# tablespoon.net
KiCad netlist of a schematic drawn in EAGLE
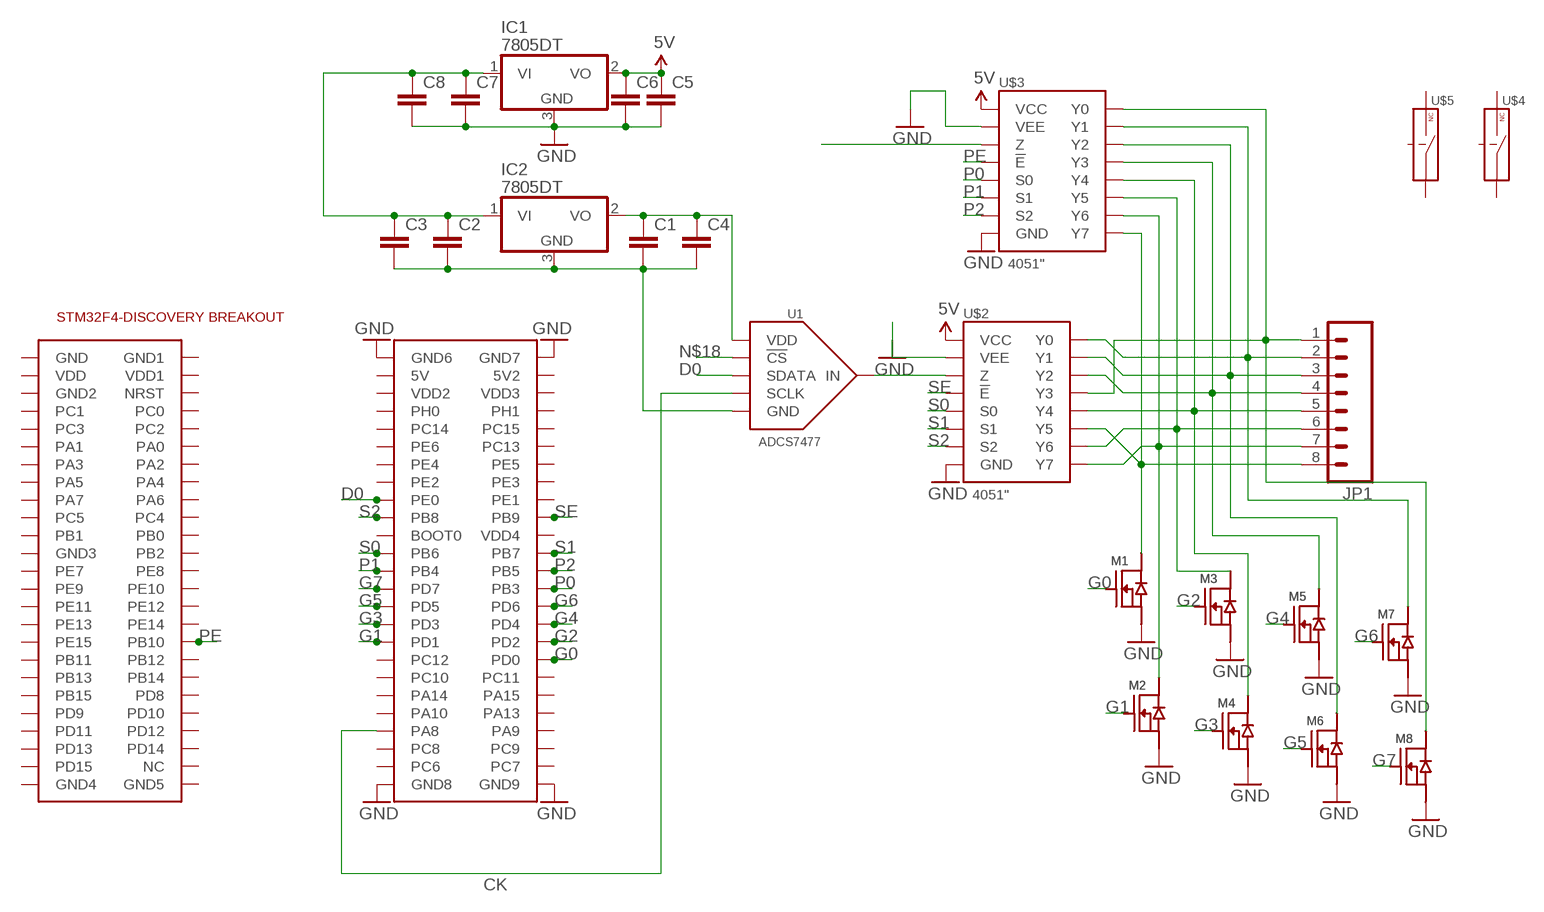
[diagram p0: schematic, sheet 1]

(export (version "E")
  (design (tool "Eeschema 10.0.6"))
  (components
    (comp (ref "C1")
      (value "C-EUC0805")
      (footprint "eagle-import:C0805")
      (libsource (lib "eagle-import") (part "C-EUC0805"))
    )
    (comp (ref "C2")
      (value "C-EUC0805")
      (footprint "eagle-import:C0805")
      (libsource (lib "eagle-import") (part "C-EUC0805"))
    )
    (comp (ref "C3")
      (value "C-EUC0805")
      (footprint "eagle-import:C0805")
      (libsource (lib "eagle-import") (part "C-EUC0805"))
    )
    (comp (ref "C4")
      (value "C-EUC0805")
      (footprint "eagle-import:C0805")
      (libsource (lib "eagle-import") (part "C-EUC0805"))
    )
    (comp (ref "C5")
      (value "C-EUC0805")
      (footprint "eagle-import:C0805")
      (libsource (lib "eagle-import") (part "C-EUC0805"))
    )
    (comp (ref "C6")
      (value "C-EUC0805")
      (footprint "eagle-import:C0805")
      (libsource (lib "eagle-import") (part "C-EUC0805"))
    )
    (comp (ref "C7")
      (value "C-EUC0805")
      (footprint "eagle-import:C0805")
      (libsource (lib "eagle-import") (part "C-EUC0805"))
    )
    (comp (ref "C8")
      (value "C-EUC0805")
      (footprint "eagle-import:C0805")
      (libsource (lib "eagle-import") (part "C-EUC0805"))
    )
    (comp (ref "IC1")
      (value "7805DT")
      (footprint "eagle-import:TO252")
      (libsource (lib "eagle-import") (part "78DT05"))
    )
    (comp (ref "IC2")
      (value "7805DT")
      (footprint "eagle-import:TO252")
      (libsource (lib "eagle-import") (part "78DT05"))
    )
    (comp (ref "JP1")
      (value "M08LONGPADS")
      (footprint "eagle-import:1X08_LONGPADS")
      (libsource (lib "eagle-import") (part "M08LONGPADS"))
    )
    (comp (ref "M1")
      (value "N-FET")
      (footprint "eagle-import:SOT23-3")
      (libsource (lib "eagle-import") (part "N-FET"))
    )
    (comp (ref "M2")
      (value "N-FET")
      (footprint "eagle-import:SOT23-3")
      (libsource (lib "eagle-import") (part "N-FET"))
    )
    (comp (ref "M3")
      (value "N-FET")
      (footprint "eagle-import:SOT23-3")
      (libsource (lib "eagle-import") (part "N-FET"))
    )
    (comp (ref "M4")
      (value "N-FET")
      (footprint "eagle-import:SOT23-3")
      (libsource (lib "eagle-import") (part "N-FET"))
    )
    (comp (ref "M5")
      (value "N-FET")
      (footprint "eagle-import:SOT23-3")
      (libsource (lib "eagle-import") (part "N-FET"))
    )
    (comp (ref "M6")
      (value "N-FET")
      (footprint "eagle-import:SOT23-3")
      (libsource (lib "eagle-import") (part "N-FET"))
    )
    (comp (ref "M7")
      (value "N-FET")
      (footprint "eagle-import:SOT23-3")
      (libsource (lib "eagle-import") (part "N-FET"))
    )
    (comp (ref "M8")
      (value "N-FET")
      (footprint "eagle-import:SOT23-3")
      (libsource (lib "eagle-import") (part "N-FET"))
    )
    (comp (ref "U$1")
      (value "STM32F4-DISCOVERY")
      (footprint "eagle-import:STM32F4-DISCOVERY")
      (libsource (lib "eagle-import") (part "STM32F4-DISCOVERY"))
    )
    (comp (ref "U$2")
      (value "4051\"")
      (footprint "eagle-import:TSSOP-16")
      (libsource (lib "eagle-import") (part "4051{dblquote}"))
    )
    (comp (ref "U$3")
      (value "4051\"")
      (footprint "eagle-import:TSSOP-16")
      (libsource (lib "eagle-import") (part "4051{dblquote}"))
    )
    (comp (ref "U$4")
      (value "DG467")
      (footprint "eagle-import:TSSOP-6")
      (libsource (lib "eagle-import") (part "DG467"))
    )
    (comp (ref "U$5")
      (value "DG467")
      (footprint "eagle-import:TSSOP-6")
      (libsource (lib "eagle-import") (part "DG467"))
    )
    (comp (ref "U1")
      (value "ADCS7477")
      (footprint "eagle-import:SOT-23-6")
      (libsource (lib "eagle-import") (part "ADCS7477"))
    )
  )
  (nets
    (net (code "1") (name "/CK") (class "Default")
      (node (ref "U$1") (pin "P$93") (pinfunction "PA8_P$93") (pintype "bidirectional"))
      (node (ref "U1") (pin "P$4") (pinfunction "SCLK_P$4") (pintype "bidirectional"))
    )
    (net (code "2") (name "/D0") (class "Default")
      (node (ref "U$1") (pin "P$67") (pinfunction "PE0_P$67") (pintype "bidirectional"))
      (node (ref "U1") (pin "P$5") (pinfunction "SDATA_P$5") (pintype "bidirectional"))
    )
    (net (code "3") (name "/G0") (class "Default")
      (node (ref "M1") (pin "1") (pinfunction "G_1") (pintype "bidirectional"))
      (node (ref "U$1") (pin "P$86") (pinfunction "PD0_P$86") (pintype "bidirectional"))
    )
    (net (code "4") (name "/G1") (class "Default")
      (node (ref "M2") (pin "1") (pinfunction "G_1") (pintype "bidirectional"))
      (node (ref "U$1") (pin "P$83") (pinfunction "PD1_P$83") (pintype "bidirectional"))
    )
    (net (code "5") (name "/G2") (class "Default")
      (node (ref "M3") (pin "1") (pinfunction "G_1") (pintype "bidirectional"))
      (node (ref "U$1") (pin "P$84") (pinfunction "PD2_P$84") (pintype "bidirectional"))
    )
    (net (code "6") (name "/G3") (class "Default")
      (node (ref "M4") (pin "1") (pinfunction "G_1") (pintype "bidirectional"))
      (node (ref "U$1") (pin "P$81") (pinfunction "PD3_P$81") (pintype "bidirectional"))
    )
    (net (code "7") (name "/G4") (class "Default")
      (node (ref "M5") (pin "1") (pinfunction "G_1") (pintype "bidirectional"))
      (node (ref "U$1") (pin "P$82") (pinfunction "PD4_P$82") (pintype "bidirectional"))
    )
    (net (code "8") (name "/G5") (class "Default")
      (node (ref "M6") (pin "1") (pinfunction "G_1") (pintype "bidirectional"))
      (node (ref "U$1") (pin "P$79") (pinfunction "PD5_P$79") (pintype "bidirectional"))
    )
    (net (code "9") (name "/G6") (class "Default")
      (node (ref "M7") (pin "1") (pinfunction "G_1") (pintype "bidirectional"))
      (node (ref "U$1") (pin "P$80") (pinfunction "PD6_P$80") (pintype "bidirectional"))
    )
    (net (code "10") (name "/G7") (class "Default")
      (node (ref "M8") (pin "1") (pinfunction "G_1") (pintype "bidirectional"))
      (node (ref "U$1") (pin "P$77") (pinfunction "PD7_P$77") (pintype "bidirectional"))
    )
    (net (code "11") (name "/N$18") (class "Default")
      (node (ref "U1") (pin "P$6") (pinfunction "~{CS}_P$6") (pintype "bidirectional"))
    )
    (net (code "12") (name "/P0") (class "Default")
      (node (ref "U$1") (pin "P$78") (pinfunction "PB3_P$78") (pintype "bidirectional"))
      (node (ref "U$3") (pin "P$11") (pinfunction "S0_P$11") (pintype "bidirectional"))
    )
    (net (code "13") (name "/P1") (class "Default")
      (node (ref "U$1") (pin "P$75") (pinfunction "PB4_P$75") (pintype "bidirectional"))
      (node (ref "U$3") (pin "P$10") (pinfunction "S1_P$10") (pintype "bidirectional"))
    )
    (net (code "14") (name "/P2") (class "Default")
      (node (ref "U$1") (pin "P$76") (pinfunction "PB5_P$76") (pintype "bidirectional"))
      (node (ref "U$3") (pin "P$9") (pinfunction "S2_P$9") (pintype "bidirectional"))
    )
    (net (code "15") (name "/PE") (class "Default")
      (node (ref "U$1") (pin "P$34") (pinfunction "PB10_P$34") (pintype "bidirectional"))
      (node (ref "U$3") (pin "P$6") (pinfunction "~{E}_P$6") (pintype "bidirectional"))
    )
    (net (code "16") (name "/S0") (class "Default")
      (node (ref "U$1") (pin "P$73") (pinfunction "PB6_P$73") (pintype "bidirectional"))
      (node (ref "U$2") (pin "P$11") (pinfunction "S0_P$11") (pintype "bidirectional"))
    )
    (net (code "17") (name "/S1") (class "Default")
      (node (ref "U$1") (pin "P$74") (pinfunction "PB7_P$74") (pintype "bidirectional"))
      (node (ref "U$2") (pin "P$10") (pinfunction "S1_P$10") (pintype "bidirectional"))
    )
    (net (code "18") (name "/S2") (class "Default")
      (node (ref "U$1") (pin "P$69") (pinfunction "PB8_P$69") (pintype "bidirectional"))
      (node (ref "U$2") (pin "P$9") (pinfunction "S2_P$9") (pintype "bidirectional"))
    )
    (net (code "19") (name "/SE") (class "Default")
      (node (ref "U$1") (pin "P$70") (pinfunction "PB9_P$70") (pintype "bidirectional"))
      (node (ref "U$2") (pin "P$6") (pinfunction "~{E}_P$6") (pintype "bidirectional"))
    )
    (net (code "20") (name "5V") (class "Default")
      (node (ref "C5") (pin "1") (pinfunction "1_1") (pintype "passive"))
      (node (ref "C6") (pin "1") (pinfunction "1_1") (pintype "passive"))
      (node (ref "IC1") (pin "2") (pinfunction "VO_2") (pintype "passive"))
      (node (ref "U$2") (pin "P$16") (pinfunction "VCC_P$16") (pintype "bidirectional"))
      (node (ref "U$3") (pin "P$16") (pinfunction "VCC_P$16") (pintype "bidirectional"))
    )
    (net (code "21") (name "GND") (class "Default")
      (node (ref "C5") (pin "2") (pinfunction "2_2") (pintype "passive"))
      (node (ref "C6") (pin "2") (pinfunction "2_2") (pintype "passive"))
      (node (ref "C7") (pin "2") (pinfunction "2_2") (pintype "passive"))
      (node (ref "C8") (pin "2") (pinfunction "2_2") (pintype "passive"))
      (node (ref "IC1") (pin "3") (pinfunction "GND_3") (pintype "passive"))
      (node (ref "M1") (pin "2") (pinfunction "S_2") (pintype "bidirectional"))
      (node (ref "M2") (pin "2") (pinfunction "S_2") (pintype "bidirectional"))
      (node (ref "M3") (pin "2") (pinfunction "S_2") (pintype "bidirectional"))
      (node (ref "M4") (pin "2") (pinfunction "S_2") (pintype "bidirectional"))
      (node (ref "M5") (pin "2") (pinfunction "S_2") (pintype "bidirectional"))
      (node (ref "M6") (pin "2") (pinfunction "S_2") (pintype "bidirectional"))
      (node (ref "M7") (pin "2") (pinfunction "S_2") (pintype "bidirectional"))
      (node (ref "M8") (pin "2") (pinfunction "S_2") (pintype "bidirectional"))
      (node (ref "U$1") (pin "P$100") (pinfunction "GND9_P$100") (pintype "bidirectional"))
      (node (ref "U$1") (pin "P$51") (pinfunction "GND6_P$51") (pintype "bidirectional"))
      (node (ref "U$1") (pin "P$52") (pinfunction "GND7_P$52") (pintype "bidirectional"))
      (node (ref "U$1") (pin "P$99") (pinfunction "GND8_P$99") (pintype "bidirectional"))
      (node (ref "U$2") (pin "P$7") (pinfunction "VEE_P$7") (pintype "bidirectional"))
      (node (ref "U$2") (pin "P$8") (pinfunction "GND_P$8") (pintype "bidirectional"))
      (node (ref "U$3") (pin "P$7") (pinfunction "VEE_P$7") (pintype "bidirectional"))
      (node (ref "U$3") (pin "P$8") (pinfunction "GND_P$8") (pintype "bidirectional"))
    )
    (net (code "22") (name "Net-(IC1-VI)") (class "Default")
      (node (ref "C2") (pin "1") (pinfunction "1_1") (pintype "passive"))
      (node (ref "C3") (pin "1") (pinfunction "1_1") (pintype "passive"))
      (node (ref "C7") (pin "1") (pinfunction "1_1") (pintype "passive"))
      (node (ref "C8") (pin "1") (pinfunction "1_1") (pintype "passive"))
      (node (ref "IC1") (pin "1") (pinfunction "VI_1") (pintype "input"))
      (node (ref "IC2") (pin "1") (pinfunction "VI_1") (pintype "input"))
    )
    (net (code "23") (name "Net-(IC2-GND)") (class "Default")
      (node (ref "C1") (pin "2") (pinfunction "2_2") (pintype "passive"))
      (node (ref "C2") (pin "2") (pinfunction "2_2") (pintype "passive"))
      (node (ref "C3") (pin "2") (pinfunction "2_2") (pintype "passive"))
      (node (ref "C4") (pin "2") (pinfunction "2_2") (pintype "passive"))
      (node (ref "IC2") (pin "3") (pinfunction "GND_3") (pintype "passive"))
      (node (ref "U1") (pin "P$2") (pinfunction "GND_P$2") (pintype "bidirectional"))
    )
    (net (code "24") (name "Net-(IC2-VO)") (class "Default")
      (node (ref "C1") (pin "1") (pinfunction "1_1") (pintype "passive"))
      (node (ref "C4") (pin "1") (pinfunction "1_1") (pintype "passive"))
      (node (ref "IC2") (pin "2") (pinfunction "VO_2") (pintype "passive"))
      (node (ref "U1") (pin "P$1") (pinfunction "VDD_P$1") (pintype "bidirectional"))
    )
    (net (code "25") (name "Net-(M1-D)") (class "Default")
      (node (ref "JP1") (pin "8") (pinfunction "8_8") (pintype "passive"))
      (node (ref "M1") (pin "3") (pinfunction "D_3") (pintype "bidirectional"))
      (node (ref "U$2") (pin "P$5") (pinfunction "Y5_P$5") (pintype "bidirectional"))
      (node (ref "U$3") (pin "P$4") (pinfunction "Y7_P$4") (pintype "bidirectional"))
    )
    (net (code "26") (name "Net-(M2-D)") (class "Default")
      (node (ref "JP1") (pin "7") (pinfunction "7_7") (pintype "passive"))
      (node (ref "M2") (pin "3") (pinfunction "D_3") (pintype "bidirectional"))
      (node (ref "U$2") (pin "P$4") (pinfunction "Y7_P$4") (pintype "bidirectional"))
      (node (ref "U$3") (pin "P$2") (pinfunction "Y6_P$2") (pintype "bidirectional"))
    )
    (net (code "27") (name "Net-(M3-D)") (class "Default")
      (node (ref "JP1") (pin "6") (pinfunction "6_6") (pintype "passive"))
      (node (ref "M3") (pin "3") (pinfunction "D_3") (pintype "bidirectional"))
      (node (ref "U$2") (pin "P$2") (pinfunction "Y6_P$2") (pintype "bidirectional"))
      (node (ref "U$3") (pin "P$5") (pinfunction "Y5_P$5") (pintype "bidirectional"))
    )
    (net (code "28") (name "Net-(M4-D)") (class "Default")
      (node (ref "JP1") (pin "5") (pinfunction "5_5") (pintype "passive"))
      (node (ref "M4") (pin "3") (pinfunction "D_3") (pintype "bidirectional"))
      (node (ref "U$2") (pin "P$1") (pinfunction "Y4_P$1") (pintype "bidirectional"))
      (node (ref "U$3") (pin "P$1") (pinfunction "Y4_P$1") (pintype "bidirectional"))
    )
    (net (code "29") (name "Net-(M5-D)") (class "Default")
      (node (ref "JP1") (pin "4") (pinfunction "4_4") (pintype "passive"))
      (node (ref "M5") (pin "3") (pinfunction "D_3") (pintype "bidirectional"))
      (node (ref "U$2") (pin "P$15") (pinfunction "Y2_P$15") (pintype "bidirectional"))
      (node (ref "U$3") (pin "P$12") (pinfunction "Y3_P$12") (pintype "bidirectional"))
    )
    (net (code "30") (name "Net-(M6-D)") (class "Default")
      (node (ref "JP1") (pin "3") (pinfunction "3_3") (pintype "passive"))
      (node (ref "M6") (pin "3") (pinfunction "D_3") (pintype "bidirectional"))
      (node (ref "U$2") (pin "P$14") (pinfunction "Y1_P$14") (pintype "bidirectional"))
      (node (ref "U$3") (pin "P$15") (pinfunction "Y2_P$15") (pintype "bidirectional"))
    )
    (net (code "31") (name "Net-(M7-D)") (class "Default")
      (node (ref "JP1") (pin "2") (pinfunction "2_2") (pintype "passive"))
      (node (ref "M7") (pin "3") (pinfunction "D_3") (pintype "bidirectional"))
      (node (ref "U$2") (pin "P$13") (pinfunction "Y0_P$13") (pintype "bidirectional"))
      (node (ref "U$3") (pin "P$14") (pinfunction "Y1_P$14") (pintype "bidirectional"))
    )
    (net (code "32") (name "Net-(M8-D)") (class "Default")
      (node (ref "JP1") (pin "1") (pinfunction "1_1") (pintype "passive"))
      (node (ref "M8") (pin "3") (pinfunction "D_3") (pintype "bidirectional"))
      (node (ref "U$2") (pin "P$12") (pinfunction "Y3_P$12") (pintype "bidirectional"))
      (node (ref "U$3") (pin "P$13") (pinfunction "Y0_P$13") (pintype "bidirectional"))
    )
    (net (code "33") (name "Net-(U$2-Z)") (class "Default")
      (node (ref "U$2") (pin "P$3") (pinfunction "Z_P$3") (pintype "bidirectional"))
      (node (ref "U1") (pin "P$3") (pinfunction "IN_P$3") (pintype "bidirectional"))
    )
    (net (code "34") (name "unconnected-(U$1-5V-PadP$53)") (class "Default")
      (node (ref "U$1") (pin "P$53") (pinfunction "5V_P$53") (pintype "bidirectional"))
    )
    (net (code "35") (name "unconnected-(U$1-5V2-PadP$54)") (class "Default")
      (node (ref "U$1") (pin "P$54") (pinfunction "5V2_P$54") (pintype "bidirectional"))
    )
    (net (code "36") (name "unconnected-(U$1-BOOT0-PadP$71)") (class "Default")
      (node (ref "U$1") (pin "P$71") (pinfunction "BOOT0_P$71") (pintype "bidirectional"))
    )
    (net (code "37") (name "unconnected-(U$1-GND-PadP$1)") (class "Default")
      (node (ref "U$1") (pin "P$1") (pinfunction "GND_P$1") (pintype "bidirectional"))
    )
    (net (code "38") (name "unconnected-(U$1-GND1-PadP$2)") (class "Default")
      (node (ref "U$1") (pin "P$2") (pinfunction "GND1_P$2") (pintype "bidirectional"))
    )
    (net (code "39") (name "unconnected-(U$1-GND2-PadP$5)") (class "Default")
      (node (ref "U$1") (pin "P$5") (pinfunction "GND2_P$5") (pintype "bidirectional"))
    )
    (net (code "40") (name "unconnected-(U$1-GND3-PadP$23)") (class "Default")
      (node (ref "U$1") (pin "P$23") (pinfunction "GND3_P$23") (pintype "bidirectional"))
    )
    (net (code "41") (name "unconnected-(U$1-GND4-PadP$49)") (class "Default")
      (node (ref "U$1") (pin "P$49") (pinfunction "GND4_P$49") (pintype "bidirectional"))
    )
    (net (code "42") (name "unconnected-(U$1-GND5-PadP$50)") (class "Default")
      (node (ref "U$1") (pin "P$50") (pinfunction "GND5_P$50") (pintype "bidirectional"))
    )
    (net (code "43") (name "unconnected-(U$1-NC-PadP$48)") (class "Default")
      (node (ref "U$1") (pin "P$48") (pinfunction "NC_P$48") (pintype "bidirectional"))
    )
    (net (code "44") (name "unconnected-(U$1-NRST-PadP$6)") (class "Default")
      (node (ref "U$1") (pin "P$6") (pinfunction "NRST_P$6") (pintype "bidirectional"))
    )
    (net (code "45") (name "unconnected-(U$1-PA0-PadP$12)") (class "Default")
      (node (ref "U$1") (pin "P$12") (pinfunction "PA0_P$12") (pintype "bidirectional"))
    )
    (net (code "46") (name "unconnected-(U$1-PA1-PadP$11)") (class "Default")
      (node (ref "U$1") (pin "P$11") (pinfunction "PA1_P$11") (pintype "bidirectional"))
    )
    (net (code "47") (name "unconnected-(U$1-PA2-PadP$14)") (class "Default")
      (node (ref "U$1") (pin "P$14") (pinfunction "PA2_P$14") (pintype "bidirectional"))
    )
    (net (code "48") (name "unconnected-(U$1-PA3-PadP$13)") (class "Default")
      (node (ref "U$1") (pin "P$13") (pinfunction "PA3_P$13") (pintype "bidirectional"))
    )
    (net (code "49") (name "unconnected-(U$1-PA4-PadP$16)") (class "Default")
      (node (ref "U$1") (pin "P$16") (pinfunction "PA4_P$16") (pintype "bidirectional"))
    )
    (net (code "50") (name "unconnected-(U$1-PA5-PadP$15)") (class "Default")
      (node (ref "U$1") (pin "P$15") (pinfunction "PA5_P$15") (pintype "bidirectional"))
    )
    (net (code "51") (name "unconnected-(U$1-PA6-PadP$18)") (class "Default")
      (node (ref "U$1") (pin "P$18") (pinfunction "PA6_P$18") (pintype "bidirectional"))
    )
    (net (code "52") (name "unconnected-(U$1-PA7-PadP$17)") (class "Default")
      (node (ref "U$1") (pin "P$17") (pinfunction "PA7_P$17") (pintype "bidirectional"))
    )
    (net (code "53") (name "unconnected-(U$1-PA9-PadP$94)") (class "Default")
      (node (ref "U$1") (pin "P$94") (pinfunction "PA9_P$94") (pintype "bidirectional"))
    )
    (net (code "54") (name "unconnected-(U$1-PA10-PadP$91)") (class "Default")
      (node (ref "U$1") (pin "P$91") (pinfunction "PA10_P$91") (pintype "bidirectional"))
    )
    (net (code "55") (name "unconnected-(U$1-PA13-PadP$92)") (class "Default")
      (node (ref "U$1") (pin "P$92") (pinfunction "PA13_P$92") (pintype "bidirectional"))
    )
    (net (code "56") (name "unconnected-(U$1-PA14-PadP$89)") (class "Default")
      (node (ref "U$1") (pin "P$89") (pinfunction "PA14_P$89") (pintype "bidirectional"))
    )
    (net (code "57") (name "unconnected-(U$1-PA15-PadP$90)") (class "Default")
      (node (ref "U$1") (pin "P$90") (pinfunction "PA15_P$90") (pintype "bidirectional"))
    )
    (net (code "58") (name "unconnected-(U$1-PB0-PadP$22)") (class "Default")
      (node (ref "U$1") (pin "P$22") (pinfunction "PB0_P$22") (pintype "bidirectional"))
    )
    (net (code "59") (name "unconnected-(U$1-PB1-PadP$21)") (class "Default")
      (node (ref "U$1") (pin "P$21") (pinfunction "PB1_P$21") (pintype "bidirectional"))
    )
    (net (code "60") (name "unconnected-(U$1-PB2-PadP$24)") (class "Default")
      (node (ref "U$1") (pin "P$24") (pinfunction "PB2_P$24") (pintype "bidirectional"))
    )
    (net (code "61") (name "unconnected-(U$1-PB11-PadP$35)") (class "Default")
      (node (ref "U$1") (pin "P$35") (pinfunction "PB11_P$35") (pintype "bidirectional"))
    )
    (net (code "62") (name "unconnected-(U$1-PB12-PadP$36)") (class "Default")
      (node (ref "U$1") (pin "P$36") (pinfunction "PB12_P$36") (pintype "bidirectional"))
    )
    (net (code "63") (name "unconnected-(U$1-PB13-PadP$37)") (class "Default")
      (node (ref "U$1") (pin "P$37") (pinfunction "PB13_P$37") (pintype "bidirectional"))
    )
    (net (code "64") (name "unconnected-(U$1-PB14-PadP$38)") (class "Default")
      (node (ref "U$1") (pin "P$38") (pinfunction "PB14_P$38") (pintype "bidirectional"))
    )
    (net (code "65") (name "unconnected-(U$1-PB15-PadP$39)") (class "Default")
      (node (ref "U$1") (pin "P$39") (pinfunction "PB15_P$39") (pintype "bidirectional"))
    )
    (net (code "66") (name "unconnected-(U$1-PC0-PadP$8)") (class "Default")
      (node (ref "U$1") (pin "P$8") (pinfunction "PC0_P$8") (pintype "bidirectional"))
    )
    (net (code "67") (name "unconnected-(U$1-PC1-PadP$7)") (class "Default")
      (node (ref "U$1") (pin "P$7") (pinfunction "PC1_P$7") (pintype "bidirectional"))
    )
    (net (code "68") (name "unconnected-(U$1-PC2-PadP$10)") (class "Default")
      (node (ref "U$1") (pin "P$10") (pinfunction "PC2_P$10") (pintype "bidirectional"))
    )
    (net (code "69") (name "unconnected-(U$1-PC3-PadP$9)") (class "Default")
      (node (ref "U$1") (pin "P$9") (pinfunction "PC3_P$9") (pintype "bidirectional"))
    )
    (net (code "70") (name "unconnected-(U$1-PC4-PadP$20)") (class "Default")
      (node (ref "U$1") (pin "P$20") (pinfunction "PC4_P$20") (pintype "bidirectional"))
    )
    (net (code "71") (name "unconnected-(U$1-PC5-PadP$19)") (class "Default")
      (node (ref "U$1") (pin "P$19") (pinfunction "PC5_P$19") (pintype "bidirectional"))
    )
    (net (code "72") (name "unconnected-(U$1-PC6-PadP$97)") (class "Default")
      (node (ref "U$1") (pin "P$97") (pinfunction "PC6_P$97") (pintype "bidirectional"))
    )
    (net (code "73") (name "unconnected-(U$1-PC7-PadP$98)") (class "Default")
      (node (ref "U$1") (pin "P$98") (pinfunction "PC7_P$98") (pintype "bidirectional"))
    )
    (net (code "74") (name "unconnected-(U$1-PC8-PadP$95)") (class "Default")
      (node (ref "U$1") (pin "P$95") (pinfunction "PC8_P$95") (pintype "bidirectional"))
    )
    (net (code "75") (name "unconnected-(U$1-PC9-PadP$96)") (class "Default")
      (node (ref "U$1") (pin "P$96") (pinfunction "PC9_P$96") (pintype "bidirectional"))
    )
    (net (code "76") (name "unconnected-(U$1-PC10-PadP$87)") (class "Default")
      (node (ref "U$1") (pin "P$87") (pinfunction "PC10_P$87") (pintype "bidirectional"))
    )
    (net (code "77") (name "unconnected-(U$1-PC11-PadP$88)") (class "Default")
      (node (ref "U$1") (pin "P$88") (pinfunction "PC11_P$88") (pintype "bidirectional"))
    )
    (net (code "78") (name "unconnected-(U$1-PC12-PadP$85)") (class "Default")
      (node (ref "U$1") (pin "P$85") (pinfunction "PC12_P$85") (pintype "bidirectional"))
    )
    (net (code "79") (name "unconnected-(U$1-PC13-PadP$62)") (class "Default")
      (node (ref "U$1") (pin "P$62") (pinfunction "PC13_P$62") (pintype "bidirectional"))
    )
    (net (code "80") (name "unconnected-(U$1-PC14-PadP$59)") (class "Default")
      (node (ref "U$1") (pin "P$59") (pinfunction "PC14_P$59") (pintype "bidirectional"))
    )
    (net (code "81") (name "unconnected-(U$1-PC15-PadP$60)") (class "Default")
      (node (ref "U$1") (pin "P$60") (pinfunction "PC15_P$60") (pintype "bidirectional"))
    )
    (net (code "82") (name "unconnected-(U$1-PD8-PadP$40)") (class "Default")
      (node (ref "U$1") (pin "P$40") (pinfunction "PD8_P$40") (pintype "bidirectional"))
    )
    (net (code "83") (name "unconnected-(U$1-PD9-PadP$41)") (class "Default")
      (node (ref "U$1") (pin "P$41") (pinfunction "PD9_P$41") (pintype "bidirectional"))
    )
    (net (code "84") (name "unconnected-(U$1-PD10-PadP$42)") (class "Default")
      (node (ref "U$1") (pin "P$42") (pinfunction "PD10_P$42") (pintype "bidirectional"))
    )
    (net (code "85") (name "unconnected-(U$1-PD11-PadP$43)") (class "Default")
      (node (ref "U$1") (pin "P$43") (pinfunction "PD11_P$43") (pintype "bidirectional"))
    )
    (net (code "86") (name "unconnected-(U$1-PD12-PadP$44)") (class "Default")
      (node (ref "U$1") (pin "P$44") (pinfunction "PD12_P$44") (pintype "bidirectional"))
    )
    (net (code "87") (name "unconnected-(U$1-PD13-PadP$45)") (class "Default")
      (node (ref "U$1") (pin "P$45") (pinfunction "PD13_P$45") (pintype "bidirectional"))
    )
    (net (code "88") (name "unconnected-(U$1-PD14-PadP$46)") (class "Default")
      (node (ref "U$1") (pin "P$46") (pinfunction "PD14_P$46") (pintype "bidirectional"))
    )
    (net (code "89") (name "unconnected-(U$1-PD15-PadP$47)") (class "Default")
      (node (ref "U$1") (pin "P$47") (pinfunction "PD15_P$47") (pintype "bidirectional"))
    )
    (net (code "90") (name "unconnected-(U$1-PE1-PadP$68)") (class "Default")
      (node (ref "U$1") (pin "P$68") (pinfunction "PE1_P$68") (pintype "bidirectional"))
    )
    (net (code "91") (name "unconnected-(U$1-PE2-PadP$65)") (class "Default")
      (node (ref "U$1") (pin "P$65") (pinfunction "PE2_P$65") (pintype "bidirectional"))
    )
    (net (code "92") (name "unconnected-(U$1-PE3-PadP$66)") (class "Default")
      (node (ref "U$1") (pin "P$66") (pinfunction "PE3_P$66") (pintype "bidirectional"))
    )
    (net (code "93") (name "unconnected-(U$1-PE4-PadP$63)") (class "Default")
      (node (ref "U$1") (pin "P$63") (pinfunction "PE4_P$63") (pintype "bidirectional"))
    )
    (net (code "94") (name "unconnected-(U$1-PE5-PadP$64)") (class "Default")
      (node (ref "U$1") (pin "P$64") (pinfunction "PE5_P$64") (pintype "bidirectional"))
    )
    (net (code "95") (name "unconnected-(U$1-PE6-PadP$61)") (class "Default")
      (node (ref "U$1") (pin "P$61") (pinfunction "PE6_P$61") (pintype "bidirectional"))
    )
    (net (code "96") (name "unconnected-(U$1-PE7-PadP$25)") (class "Default")
      (node (ref "U$1") (pin "P$25") (pinfunction "PE7_P$25") (pintype "bidirectional"))
    )
    (net (code "97") (name "unconnected-(U$1-PE8-PadP$26)") (class "Default")
      (node (ref "U$1") (pin "P$26") (pinfunction "PE8_P$26") (pintype "bidirectional"))
    )
    (net (code "98") (name "unconnected-(U$1-PE9-PadP$27)") (class "Default")
      (node (ref "U$1") (pin "P$27") (pinfunction "PE9_P$27") (pintype "bidirectional"))
    )
    (net (code "99") (name "unconnected-(U$1-PE10-PadP$28)") (class "Default")
      (node (ref "U$1") (pin "P$28") (pinfunction "PE10_P$28") (pintype "bidirectional"))
    )
    (net (code "100") (name "unconnected-(U$1-PE11-PadP$29)") (class "Default")
      (node (ref "U$1") (pin "P$29") (pinfunction "PE11_P$29") (pintype "bidirectional"))
    )
    (net (code "101") (name "unconnected-(U$1-PE12-PadP$30)") (class "Default")
      (node (ref "U$1") (pin "P$30") (pinfunction "PE12_P$30") (pintype "bidirectional"))
    )
    (net (code "102") (name "unconnected-(U$1-PE13-PadP$31)") (class "Default")
      (node (ref "U$1") (pin "P$31") (pinfunction "PE13_P$31") (pintype "bidirectional"))
    )
    (net (code "103") (name "unconnected-(U$1-PE14-PadP$32)") (class "Default")
      (node (ref "U$1") (pin "P$32") (pinfunction "PE14_P$32") (pintype "bidirectional"))
    )
    (net (code "104") (name "unconnected-(U$1-PE15-PadP$33)") (class "Default")
      (node (ref "U$1") (pin "P$33") (pinfunction "PE15_P$33") (pintype "bidirectional"))
    )
    (net (code "105") (name "unconnected-(U$1-PH0-PadP$57)") (class "Default")
      (node (ref "U$1") (pin "P$57") (pinfunction "PH0_P$57") (pintype "bidirectional"))
    )
    (net (code "106") (name "unconnected-(U$1-PH1-PadP$58)") (class "Default")
      (node (ref "U$1") (pin "P$58") (pinfunction "PH1_P$58") (pintype "bidirectional"))
    )
    (net (code "107") (name "unconnected-(U$1-VDD-PadP$3)") (class "Default")
      (node (ref "U$1") (pin "P$3") (pinfunction "VDD_P$3") (pintype "bidirectional"))
    )
    (net (code "108") (name "unconnected-(U$1-VDD1-PadP$4)") (class "Default")
      (node (ref "U$1") (pin "P$4") (pinfunction "VDD1_P$4") (pintype "bidirectional"))
    )
    (net (code "109") (name "unconnected-(U$1-VDD2-PadP$55)") (class "Default")
      (node (ref "U$1") (pin "P$55") (pinfunction "VDD2_P$55") (pintype "bidirectional"))
    )
    (net (code "110") (name "unconnected-(U$1-VDD3-PadP$56)") (class "Default")
      (node (ref "U$1") (pin "P$56") (pinfunction "VDD3_P$56") (pintype "bidirectional"))
    )
    (net (code "111") (name "unconnected-(U$1-VDD4-PadP$72)") (class "Default")
      (node (ref "U$1") (pin "P$72") (pinfunction "VDD4_P$72") (pintype "bidirectional"))
    )
    (net (code "112") (name "unconnected-(U$3-Z-PadP$3)") (class "Default")
      (node (ref "U$3") (pin "P$3") (pinfunction "Z_P$3") (pintype "bidirectional"))
    )
    (net (code "113") (name "unconnected-(U$4A-COM-PadP$6)") (class "Default")
      (node (ref "U$4") (pin "P$6") (pinfunction "COM_P$6") (pintype "bidirectional"))
    )
    (net (code "114") (name "unconnected-(U$4A-CTL-PadP$3)") (class "Default")
      (node (ref "U$4") (pin "P$3") (pinfunction "CTL_P$3") (pintype "bidirectional"))
    )
    (net (code "115") (name "unconnected-(U$4A-IN-PadP$1)") (class "Default")
      (node (ref "U$4") (pin "P$1") (pinfunction "IN_P$1") (pintype "bidirectional"))
    )
    (net (code "116") (name "unconnected-(U$5A-COM-PadP$6)") (class "Default")
      (node (ref "U$5") (pin "P$6") (pinfunction "COM_P$6") (pintype "bidirectional"))
    )
    (net (code "117") (name "unconnected-(U$5A-CTL-PadP$3)") (class "Default")
      (node (ref "U$5") (pin "P$3") (pinfunction "CTL_P$3") (pintype "bidirectional"))
    )
    (net (code "118") (name "unconnected-(U$5A-IN-PadP$1)") (class "Default")
      (node (ref "U$5") (pin "P$1") (pinfunction "IN_P$1") (pintype "bidirectional"))
    )
  )
)
